# Qwiic-Step.net
KiCad netlist of a schematic drawn in EAGLE
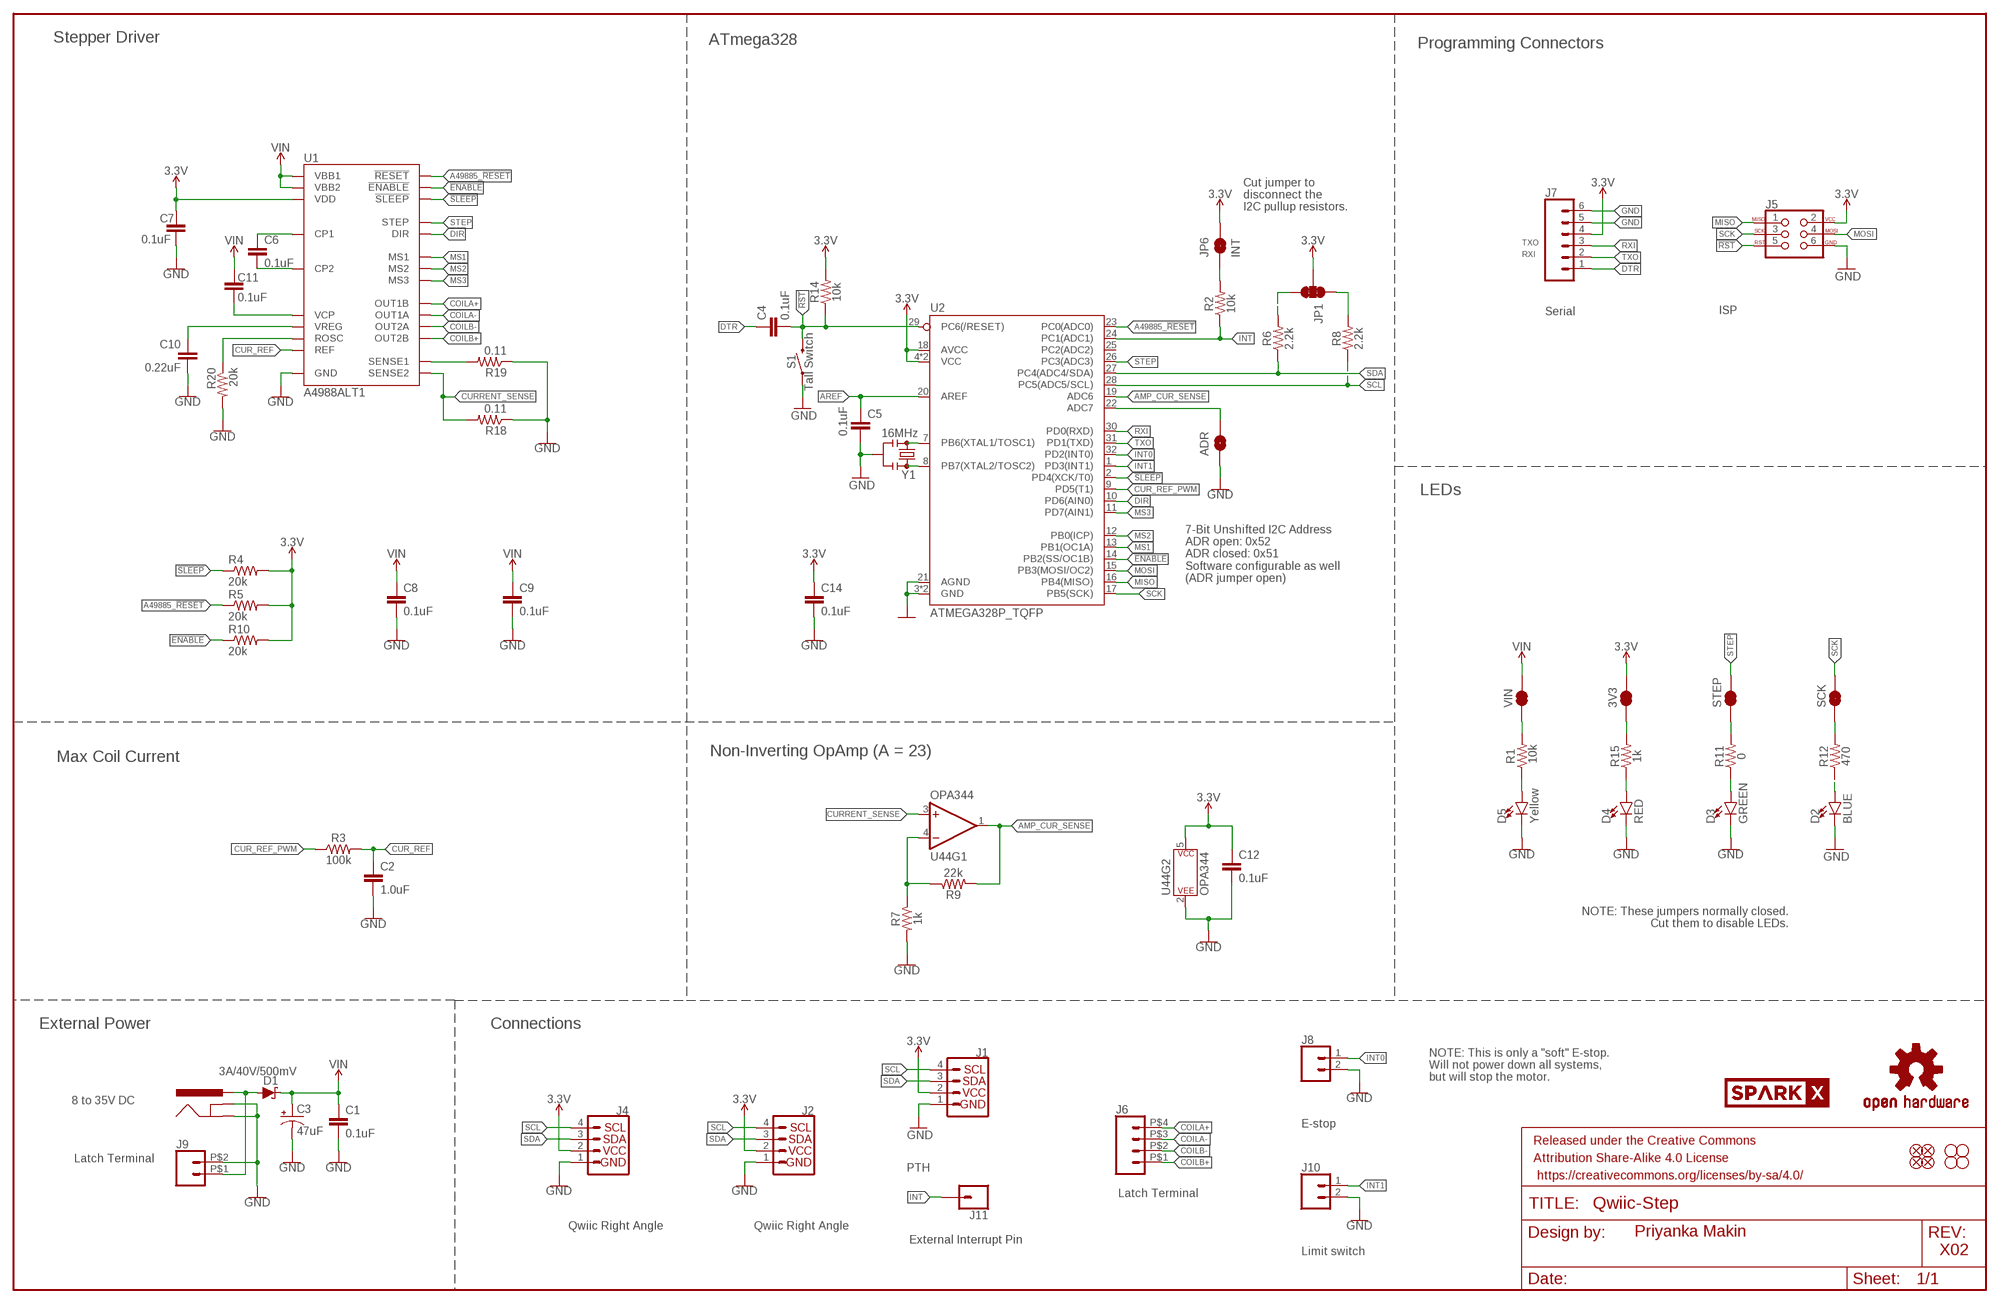
[diagram p0: schematic, sheet 1]

(export (version "E")
  (design (tool "Eeschema 10.0.6"))
  (components
    (comp (ref "3V3")
      (value "JUMPER-SMT_2_NC_TRACE_SILK")
      (footprint "eagle-import:SMT-JUMPER_2_NC_TRACE_SILK")
      (libsource (lib "eagle-import") (part "JUMPER-SMT_2_NC_TRACE_SILK"))
    )
    (comp (ref "ADR")
      (value "ADR")
      (footprint "eagle-import:SMT-JUMPER_2_NO_SILK")
      (libsource (lib "eagle-import") (part "JUMPER-SMT_2_NO_SILK"))
    )
    (comp (ref "C1")
      (value "0.1uF")
      (footprint "eagle-import:0603")
      (libsource (lib "eagle-import") (part "0.1UF-0603-100V-10%"))
    )
    (comp (ref "C2")
      (value "1.0uF")
      (footprint "eagle-import:0603")
      (libsource (lib "eagle-import") (part "1.0UF-0603-16V-10%-X7R"))
    )
    (comp (ref "C3")
      (value "47uF")
      (footprint "eagle-import:PANASONIC_D")
      (libsource (lib "eagle-import") (part "47UF-POLAR-PANASONIC_D-35V-20%"))
    )
    (comp (ref "C4")
      (value "0.1uF")
      (footprint "eagle-import:0603")
      (libsource (lib "eagle-import") (part "0.1UF-0603-100V-10%"))
    )
    (comp (ref "C5")
      (value "0.1uF")
      (footprint "eagle-import:0603")
      (libsource (lib "eagle-import") (part "0.1UF-0603-25V-(+80/-20%)"))
    )
    (comp (ref "C6")
      (value "0.1uF")
      (footprint "eagle-import:0603")
      (libsource (lib "eagle-import") (part "0.1UF-0603-100V-10%"))
    )
    (comp (ref "C7")
      (value "0.1uF")
      (footprint "eagle-import:0603")
      (libsource (lib "eagle-import") (part "0.1UF-0603-25V-(+80/-20%)"))
    )
    (comp (ref "C8")
      (value "0.1uF")
      (footprint "eagle-import:0603")
      (libsource (lib "eagle-import") (part "0.1UF-0603-100V-10%"))
    )
    (comp (ref "C9")
      (value "0.1uF")
      (footprint "eagle-import:0603")
      (libsource (lib "eagle-import") (part "0.1UF-0603-100V-10%"))
    )
    (comp (ref "C10")
      (value "0.22uF")
      (footprint "eagle-import:0603")
      (libsource (lib "eagle-import") (part "0.22UF-0603-50V-(-20/+80%)"))
    )
    (comp (ref "C11")
      (value "0.1uF")
      (footprint "eagle-import:0603")
      (libsource (lib "eagle-import") (part "0.1UF-0603-100V-10%"))
    )
    (comp (ref "C12")
      (value "0.1uF")
      (footprint "eagle-import:0603")
      (libsource (lib "eagle-import") (part "0.1UF-0603-25V-(+80/-20%)"))
    )
    (comp (ref "C14")
      (value "0.1uF")
      (footprint "eagle-import:0603")
      (libsource (lib "eagle-import") (part "0.1UF-0603-25V-(+80/-20%)"))
    )
    (comp (ref "D1")
      (value "3A/40V/500mV")
      (footprint "eagle-import:SMA-DIODE")
      (libsource (lib "eagle-import") (part "DIODE-SCHOTTKY-B340A"))
    )
    (comp (ref "D2")
      (value "BLUE")
      (footprint "eagle-import:LED-0603")
      (libsource (lib "eagle-import") (part "LED-BLUE0603"))
    )
    (comp (ref "D3")
      (value "GREEN")
      (footprint "eagle-import:LED-0603")
      (libsource (lib "eagle-import") (part "LED-GREEN0603"))
    )
    (comp (ref "D4")
      (value "RED")
      (footprint "eagle-import:LED-0603")
      (libsource (lib "eagle-import") (part "LED-RED0603"))
    )
    (comp (ref "D5")
      (value "Yellow")
      (footprint "eagle-import:LED-0603")
      (libsource (lib "eagle-import") (part "LED-YELLOW0603"))
    )
    (comp (ref "FD1")
      (value "FIDUCIAL1X2")
      (footprint "eagle-import:FIDUCIAL-1X2")
      (libsource (lib "eagle-import") (part "FIDUCIAL1X2"))
    )
    (comp (ref "FD2")
      (value "FIDUCIAL1X2")
      (footprint "eagle-import:FIDUCIAL-1X2")
      (libsource (lib "eagle-import") (part "FIDUCIAL1X2"))
    )
    (comp (ref "FD3")
      (value "FIDUCIAL1X2")
      (footprint "eagle-import:FIDUCIAL-1X2")
      (libsource (lib "eagle-import") (part "FIDUCIAL1X2"))
    )
    (comp (ref "FD4")
      (value "FIDUCIAL1X2")
      (footprint "eagle-import:FIDUCIAL-1X2")
      (libsource (lib "eagle-import") (part "FIDUCIAL1X2"))
    )
    (comp (ref "FRAME2")
      (value "FRAME-LEDGER")
      (footprint "eagle-import:CREATIVE_COMMONS")
      (libsource (lib "eagle-import") (part "FRAME-LEDGER"))
    )
    (comp (ref "J1")
      (value "PTH")
      (footprint "eagle-import:1X04_NO_SILK")
      (libsource (lib "eagle-import") (part "SparkX_I2C_STANDARD_NO_SILK"))
    )
    (comp (ref "J2")
      (value "Qwiic Right Angle")
      (footprint "eagle-import:JST04_1MM_RA")
      (libsource (lib "eagle-import") (part "I2C_STANDARDQWIIC"))
    )
    (comp (ref "J3")
      (value "5.5x2.1mm Barrel")
      (footprint "eagle-import:POWER_JACK_SMD")
      (fields (field (name "PROD_ID") "CONN-08106"))
      (libsource (lib "eagle-import") (part "POWER_JACKSMD"))
    )
    (comp (ref "J4")
      (value "Qwiic Right Angle")
      (footprint "eagle-import:JST04_1MM_RA")
      (libsource (lib "eagle-import") (part "I2C_STANDARDQWIIC"))
    )
    (comp (ref "J5")
      (value "ISP")
      (footprint "eagle-import:2X3_TEST_POINTS")
      (libsource (lib "eagle-import") (part "AVR_SPI_PROG_3X2TESTPOINTS"))
    )
    (comp (ref "J6")
      (value "CONN_04LATCH")
      (footprint "eagle-import:LATCHTERMINAL-5MM-4")
      (libsource (lib "eagle-import") (part "CONN_04LATCH"))
    )
    (comp (ref "J7")
      (value "CONN_06NO_SILK_NO_POP")
      (footprint "eagle-import:1X06_NO_SILK")
      (libsource (lib "eagle-import") (part "CONN_06NO_SILK_NO_POP"))
    )
    (comp (ref "J8")
      (value "CONN_02-JST-2MM-SMT")
      (footprint "eagle-import:JST-2-SMD")
      (libsource (lib "eagle-import") (part "CONN_02-JST-2MM-SMT"))
    )
    (comp (ref "J9")
      (value "CONN_02LATCH_2")
      (footprint "eagle-import:LATCHTERMINAL-5MM-2")
      (libsource (lib "eagle-import") (part "CONN_02LATCH_2"))
    )
    (comp (ref "J10")
      (value "CONN_02-JST-2MM-SMT")
      (footprint "eagle-import:JST-2-SMD")
      (libsource (lib "eagle-import") (part "CONN_02-JST-2MM-SMT"))
    )
    (comp (ref "J11")
      (value "CONN_01PTH_NO_SILK_YES_STOP")
      (footprint "eagle-import:1X01_NO_SILK")
      (libsource (lib "eagle-import") (part "CONN_01PTH_NO_SILK_YES_STOP"))
    )
    (comp (ref "JP1")
      (value "JUMPER-SMT_3_2-NC_TRACE_SILK")
      (footprint "eagle-import:SMT-JUMPER_3_2-NC_TRACE_SILK")
      (libsource (lib "eagle-import") (part "JUMPER-SMT_3_2-NC_TRACE_SILK"))
    )
    (comp (ref "JP6")
      (value "INT")
      (footprint "eagle-import:SMT-JUMPER_2_NC_TRACE_SILK")
      (libsource (lib "eagle-import") (part "JUMPER-SMT_2_NC_TRACE_SILK"))
    )
    (comp (ref "JP7")
      (value "STAND-OFF")
      (footprint "eagle-import:STAND-OFF")
      (libsource (lib "eagle-import") (part "STAND-OFF"))
    )
    (comp (ref "JP8")
      (value "STAND-OFF")
      (footprint "eagle-import:STAND-OFF")
      (libsource (lib "eagle-import") (part "STAND-OFF"))
    )
    (comp (ref "JP9")
      (value "STAND-OFF")
      (footprint "eagle-import:STAND-OFF")
      (libsource (lib "eagle-import") (part "STAND-OFF"))
    )
    (comp (ref "JP10")
      (value "STAND-OFF")
      (footprint "eagle-import:STAND-OFF")
      (libsource (lib "eagle-import") (part "STAND-OFF"))
    )
    (comp (ref "LOGO1")
      (value "OSHW-LOGOMINI")
      (footprint "eagle-import:OSHW-LOGO-MINI")
      (libsource (lib "eagle-import") (part "OSHW-LOGOMINI"))
    )
    (comp (ref "R1")
      (value "10k")
      (footprint "eagle-import:0603")
      (libsource (lib "eagle-import") (part "10KOHM-0603-1/10W-1%"))
    )
    (comp (ref "R2")
      (value "10k")
      (footprint "eagle-import:0603")
      (libsource (lib "eagle-import") (part "10KOHM-0603-1/10W-1%"))
    )
    (comp (ref "R3")
      (value "100k")
      (footprint "eagle-import:0603")
      (libsource (lib "eagle-import") (part "100KOHM-0603-1/10W-1%"))
    )
    (comp (ref "R4")
      (value "20k")
      (footprint "eagle-import:0603")
      (libsource (lib "eagle-import") (part "20KOHM-0603-1/10W-1%"))
    )
    (comp (ref "R5")
      (value "20k")
      (footprint "eagle-import:0603")
      (libsource (lib "eagle-import") (part "20KOHM-0603-1/10W-1%"))
    )
    (comp (ref "R6")
      (value "2.2k")
      (footprint "eagle-import:0603")
      (libsource (lib "eagle-import") (part "2.2KOHM-0603-1/10W-1%"))
    )
    (comp (ref "R7")
      (value "1k")
      (footprint "eagle-import:0603")
      (libsource (lib "eagle-import") (part "1KOHM-0603-1/10W-1%"))
    )
    (comp (ref "R8")
      (value "2.2k")
      (footprint "eagle-import:0603")
      (libsource (lib "eagle-import") (part "2.2KOHM-0603-1/10W-1%"))
    )
    (comp (ref "R9")
      (value "22k")
      (footprint "eagle-import:0603")
      (libsource (lib "eagle-import") (part "22KOHM-0603-1/10W-1%"))
    )
    (comp (ref "R10")
      (value "20k")
      (footprint "eagle-import:0603")
      (libsource (lib "eagle-import") (part "20KOHM-0603-1/10W-1%"))
    )
    (comp (ref "R11")
      (value "0")
      (footprint "eagle-import:0603")
      (libsource (lib "eagle-import") (part "0OHM-0603-1/10W"))
    )
    (comp (ref "R12")
      (value "470")
      (footprint "eagle-import:0603")
      (libsource (lib "eagle-import") (part "470OHM-0603-1/10W-1%"))
    )
    (comp (ref "R14")
      (value "10k")
      (footprint "eagle-import:0603")
      (libsource (lib "eagle-import") (part "10KOHM-0603-1/10W-1%"))
    )
    (comp (ref "R15")
      (value "1k")
      (footprint "eagle-import:0603")
      (libsource (lib "eagle-import") (part "1KOHM-0603-1/10W-1%"))
    )
    (comp (ref "R18")
      (value "0.11")
      (footprint "eagle-import:2010")
      (libsource (lib "eagle-import") (part "0.11OHM-2010-1/2W-1%"))
    )
    (comp (ref "R19")
      (value "0.11")
      (footprint "eagle-import:2010")
      (libsource (lib "eagle-import") (part "0.11OHM-2010-1/2W-1%"))
    )
    (comp (ref "R20")
      (value "20k")
      (footprint "eagle-import:0603")
      (libsource (lib "eagle-import") (part "20KOHM-0603-1/10W-1%"))
    )
    (comp (ref "S1")
      (value "Tall Switch")
      (footprint "eagle-import:TACTILE_SWITCH_SMD_5.2MM")
      (libsource (lib "eagle-import") (part "MOMENTARY-SWITCH-SPST-SMD-5.2-TALL-REDUNDANT"))
    )
    (comp (ref "SCK")
      (value "JUMPER-SMT_2_NC_TRACE_SILK")
      (footprint "eagle-import:SMT-JUMPER_2_NC_TRACE_SILK")
      (libsource (lib "eagle-import") (part "JUMPER-SMT_2_NC_TRACE_SILK"))
    )
    (comp (ref "STEP")
      (value "JUMPER-SMT_2_NC_TRACE_SILK")
      (footprint "eagle-import:SMT-JUMPER_2_NC_TRACE_SILK")
      (libsource (lib "eagle-import") (part "JUMPER-SMT_2_NC_TRACE_SILK"))
    )
    (comp (ref "U$49")
      (value "SPARKX-LOGO4")
      (footprint "eagle-import:SPARKX-MEDIUM")
      (libsource (lib "eagle-import") (part "SPARKX-LOGO4"))
    )
    (comp (ref "U1")
      (value "A4988ALT1")
      (footprint "eagle-import:QFN-28-5MM")
      (libsource (lib "eagle-import") (part "A4988ALT1"))
    )
    (comp (ref "U2")
      (value "ATMEGA328P_TQFP")
      (footprint "eagle-import:TQFP32-08")
      (libsource (lib "eagle-import") (part "ATMEGA328P_TQFP"))
    )
    (comp (ref "U44")
      (value "OPA344")
      (footprint "eagle-import:SOT23-5")
      (libsource (lib "eagle-import") (part "OPA344"))
    )
    (comp (ref "VIN")
      (value "JUMPER-SMT_2_NC_TRACE_SILK")
      (footprint "eagle-import:SMT-JUMPER_2_NC_TRACE_SILK")
      (libsource (lib "eagle-import") (part "JUMPER-SMT_2_NC_TRACE_SILK"))
    )
    (comp (ref "Y1")
      (value "16MHz")
      (footprint "eagle-import:RESONATOR-SMD-3.2X1.3")
      (libsource (lib "eagle-import") (part "RESONATOR-16MHZSMD_3.2X1.3"))
    )
  )
  (nets
    (net (code "1") (name "/A49885_~{RESET}") (class "Default")
      (node (ref "R5") (pin "1") (pinfunction "1_1") (pintype "passive"))
      (node (ref "U1") (pin "12") (pinfunction "~{RESET}_12") (pintype "input"))
      (node (ref "U2") (pin "23") (pinfunction "PC0(ADC0)_23") (pintype "bidirectional"))
    )
    (net (code "2") (name "/~{ENABLE}") (class "Default")
      (node (ref "R10") (pin "1") (pinfunction "1_1") (pintype "passive"))
      (node (ref "U1") (pin "2") (pinfunction "~{ENABLE}_2") (pintype "input"))
      (node (ref "U2") (pin "14") (pinfunction "PB2(SS/OC1B)_14") (pintype "bidirectional"))
    )
    (net (code "3") (name "/~{RST}") (class "Default")
      (node (ref "C4") (pin "2") (pinfunction "2_2") (pintype "passive"))
      (node (ref "J5") (pin "5") (pinfunction "5_5") (pintype "passive"))
      (node (ref "R14") (pin "1") (pinfunction "1_1") (pintype "passive"))
      (node (ref "S1") (pin "3") (pinfunction "2_3") (pintype "passive"))
      (node (ref "S1") (pin "4") (pinfunction "2_4") (pintype "passive"))
      (node (ref "U2") (pin "29") (pinfunction "PC6(/RESET)_29") (pintype "bidirectional"))
    )
    (net (code "4") (name "/~{SLEEP}") (class "Default")
      (node (ref "R4") (pin "1") (pinfunction "1_1") (pintype "passive"))
      (node (ref "U1") (pin "14") (pinfunction "~{SLEEP}_14") (pintype "input"))
      (node (ref "U2") (pin "2") (pinfunction "PD4(XCK/T0)_2") (pintype "bidirectional"))
    )
    (net (code "5") (name "3.3V") (class "Default")
      (node (ref "3V3") (pin "2") (pinfunction "2_2") (pintype "passive"))
      (node (ref "C12") (pin "1") (pinfunction "1_1") (pintype "passive"))
      (node (ref "C14") (pin "1") (pinfunction "1_1") (pintype "passive"))
      (node (ref "C7") (pin "1") (pinfunction "1_1") (pintype "passive"))
      (node (ref "J1") (pin "2") (pinfunction "VCC_2") (pintype "power_in"))
      (node (ref "J2") (pin "2") (pinfunction "2_2") (pintype "power_in"))
      (node (ref "J4") (pin "2") (pinfunction "2_2") (pintype "power_in"))
      (node (ref "J5") (pin "2") (pinfunction "2_2") (pintype "passive"))
      (node (ref "J7") (pin "4") (pinfunction "4_4") (pintype "passive"))
      (node (ref "JP1") (pin "2") (pinfunction "2_2") (pintype "passive"))
      (node (ref "JP6") (pin "2") (pinfunction "2_2") (pintype "passive"))
      (node (ref "R10") (pin "2") (pinfunction "2_2") (pintype "passive"))
      (node (ref "R14") (pin "2") (pinfunction "2_2") (pintype "passive"))
      (node (ref "R4") (pin "2") (pinfunction "2_2") (pintype "passive"))
      (node (ref "R5") (pin "2") (pinfunction "2_2") (pintype "passive"))
      (node (ref "U1") (pin "15") (pinfunction "VDD_15") (pintype "power_in"))
      (node (ref "U2") (pin "18") (pinfunction "AVCC_18") (pintype "bidirectional"))
      (node (ref "U2") (pin "4") (pinfunction "VCC_4") (pintype "bidirectional"))
      (node (ref "U2") (pin "6") (pinfunction "VCC_6") (pintype "bidirectional"))
      (node (ref "U44") (pin "5") (pinfunction "P$V+_5") (pintype "bidirectional"))
    )
    (net (code "6") (name "AMP_CUR_SENSE") (class "Default")
      (node (ref "R9") (pin "2") (pinfunction "2_2") (pintype "passive"))
      (node (ref "U2") (pin "19") (pinfunction "ADC6_19") (pintype "bidirectional"))
      (node (ref "U44") (pin "1") (pinfunction "OUT_1") (pintype "output"))
    )
    (net (code "7") (name "AREF") (class "Default")
      (node (ref "C5") (pin "1") (pinfunction "1_1") (pintype "passive"))
      (node (ref "U2") (pin "20") (pinfunction "AREF_20") (pintype "bidirectional"))
    )
    (net (code "8") (name "COILA+") (class "Default")
      (node (ref "J6") (pin "P$4") (pinfunction "4_P$4") (pintype "passive"))
      (node (ref "U1") (pin "21") (pinfunction "OUT1B_21") (pintype "bidirectional"))
    )
    (net (code "9") (name "COILA-") (class "Default")
      (node (ref "J6") (pin "P$3") (pinfunction "3_P$3") (pintype "passive"))
      (node (ref "U1") (pin "24") (pinfunction "OUT1A_24") (pintype "bidirectional"))
    )
    (net (code "10") (name "COILB+") (class "Default")
      (node (ref "J6") (pin "P$1") (pinfunction "1_P$1") (pintype "passive"))
      (node (ref "U1") (pin "1") (pinfunction "OUT2B_1") (pintype "bidirectional"))
    )
    (net (code "11") (name "COILB-") (class "Default")
      (node (ref "J6") (pin "P$2") (pinfunction "2_P$2") (pintype "passive"))
      (node (ref "U1") (pin "26") (pinfunction "OUT2A_26") (pintype "bidirectional"))
    )
    (net (code "12") (name "CURRENT_SENSE") (class "Default")
      (node (ref "R18") (pin "2") (pinfunction "2_2") (pintype "passive"))
      (node (ref "U1") (pin "27") (pinfunction "SENSE2_27") (pintype "bidirectional"))
      (node (ref "U44") (pin "3") (pinfunction "+IN_3") (pintype "input"))
    )
    (net (code "13") (name "CUR_REF") (class "Default")
      (node (ref "C2") (pin "1") (pinfunction "1_1") (pintype "passive"))
      (node (ref "R3") (pin "2") (pinfunction "2_2") (pintype "passive"))
      (node (ref "U1") (pin "17") (pinfunction "REF_17") (pintype "bidirectional"))
    )
    (net (code "14") (name "CUR_REF_PWM") (class "Default")
      (node (ref "R3") (pin "1") (pinfunction "1_1") (pintype "passive"))
      (node (ref "U2") (pin "9") (pinfunction "PD5(T1)_9") (pintype "bidirectional"))
    )
    (net (code "15") (name "DIR") (class "Default")
      (node (ref "U1") (pin "19") (pinfunction "DIR_19") (pintype "input"))
      (node (ref "U2") (pin "10") (pinfunction "PD6(AIN0)_10") (pintype "bidirectional"))
    )
    (net (code "16") (name "DTR") (class "Default")
      (node (ref "C4") (pin "1") (pinfunction "1_1") (pintype "passive"))
      (node (ref "J7") (pin "1") (pinfunction "1_1") (pintype "passive"))
    )
    (net (code "17") (name "GND") (class "Default")
      (node (ref "ADR") (pin "2") (pinfunction "2_2") (pintype "passive"))
      (node (ref "C1") (pin "2") (pinfunction "2_2") (pintype "passive"))
      (node (ref "C10") (pin "2") (pinfunction "2_2") (pintype "passive"))
      (node (ref "C12") (pin "2") (pinfunction "2_2") (pintype "passive"))
      (node (ref "C14") (pin "2") (pinfunction "2_2") (pintype "passive"))
      (node (ref "C2") (pin "2") (pinfunction "2_2") (pintype "passive"))
      (node (ref "C3") (pin "-") (pinfunction "-_-") (pintype "passive"))
      (node (ref "C5") (pin "2") (pinfunction "2_2") (pintype "passive"))
      (node (ref "C7") (pin "2") (pinfunction "2_2") (pintype "passive"))
      (node (ref "C8") (pin "2") (pinfunction "2_2") (pintype "passive"))
      (node (ref "C9") (pin "2") (pinfunction "2_2") (pintype "passive"))
      (node (ref "D2") (pin "C") (pinfunction "C_C") (pintype "passive"))
      (node (ref "D3") (pin "C") (pinfunction "C_C") (pintype "passive"))
      (node (ref "D4") (pin "C") (pinfunction "C_C") (pintype "passive"))
      (node (ref "D5") (pin "C") (pinfunction "C_C") (pintype "passive"))
      (node (ref "J1") (pin "1") (pinfunction "GND_1") (pintype "power_in"))
      (node (ref "J10") (pin "2") (pinfunction "1_2") (pintype "passive"))
      (node (ref "J2") (pin "1") (pinfunction "1_1") (pintype "power_in"))
      (node (ref "J3") (pin "GND") (pinfunction "GNDBREAK_GND") (pintype "bidirectional"))
      (node (ref "J3") (pin "P$4") (pinfunction "GND_P$4") (pintype "bidirectional"))
      (node (ref "J4") (pin "1") (pinfunction "1_1") (pintype "power_in"))
      (node (ref "J5") (pin "6") (pinfunction "6_6") (pintype "passive"))
      (node (ref "J7") (pin "5") (pinfunction "5_5") (pintype "passive"))
      (node (ref "J7") (pin "6") (pinfunction "6_6") (pintype "passive"))
      (node (ref "J8") (pin "2") (pinfunction "1_2") (pintype "passive"))
      (node (ref "J9") (pin "P$2") (pinfunction "2_P$2") (pintype "passive"))
      (node (ref "R18") (pin "1") (pinfunction "1_1") (pintype "passive"))
      (node (ref "R19") (pin "1") (pinfunction "1_1") (pintype "passive"))
      (node (ref "R20") (pin "2") (pinfunction "2_2") (pintype "passive"))
      (node (ref "R7") (pin "2") (pinfunction "2_2") (pintype "passive"))
      (node (ref "S1") (pin "1") (pinfunction "1_1") (pintype "passive"))
      (node (ref "S1") (pin "2") (pinfunction "1_2") (pintype "passive"))
      (node (ref "U1") (pin "18") (pinfunction "GND_18") (pintype "power_in"))
      (node (ref "U1") (pin "29") (pinfunction "GND_29") (pintype "power_in"))
      (node (ref "U1") (pin "3") (pinfunction "GND_3") (pintype "power_in"))
      (node (ref "U2") (pin "21") (pinfunction "AGND_21") (pintype "bidirectional"))
      (node (ref "U2") (pin "3") (pinfunction "GND_3") (pintype "bidirectional"))
      (node (ref "U2") (pin "5") (pinfunction "GND_5") (pintype "bidirectional"))
      (node (ref "U44") (pin "2") (pinfunction "P$V-_2") (pintype "bidirectional"))
      (node (ref "Y1") (pin "2") (pinfunction "2_2") (pintype "passive"))
    )
    (net (code "18") (name "INT") (class "Default")
      (node (ref "J11") (pin "1") (pinfunction "1_1") (pintype "passive"))
      (node (ref "R2") (pin "1") (pinfunction "1_1") (pintype "passive"))
      (node (ref "U2") (pin "24") (pinfunction "PC1(ADC1)_24") (pintype "bidirectional"))
    )
    (net (code "19") (name "INT0") (class "Default")
      (node (ref "J8") (pin "1") (pinfunction "2_1") (pintype "passive"))
      (node (ref "U2") (pin "32") (pinfunction "PD2(INT0)_32") (pintype "bidirectional"))
    )
    (net (code "20") (name "INT1") (class "Default")
      (node (ref "J10") (pin "1") (pinfunction "2_1") (pintype "passive"))
      (node (ref "U2") (pin "1") (pinfunction "PD3(INT1)_1") (pintype "bidirectional"))
    )
    (net (code "21") (name "MISO") (class "Default")
      (node (ref "J5") (pin "1") (pinfunction "1_1") (pintype "passive"))
      (node (ref "U2") (pin "16") (pinfunction "PB4(MISO)_16") (pintype "bidirectional"))
    )
    (net (code "22") (name "MOSI") (class "Default")
      (node (ref "J5") (pin "4") (pinfunction "4_4") (pintype "passive"))
      (node (ref "U2") (pin "15") (pinfunction "PB3(MOSI/OC2)_15") (pintype "bidirectional"))
    )
    (net (code "23") (name "MS1") (class "Default")
      (node (ref "U1") (pin "9") (pinfunction "MS1_9") (pintype "input"))
      (node (ref "U2") (pin "13") (pinfunction "PB1(OC1A)_13") (pintype "bidirectional"))
    )
    (net (code "24") (name "MS2") (class "Default")
      (node (ref "U1") (pin "10") (pinfunction "MS2_10") (pintype "input"))
      (node (ref "U2") (pin "12") (pinfunction "PB0(ICP)_12") (pintype "bidirectional"))
    )
    (net (code "25") (name "MS3") (class "Default")
      (node (ref "U1") (pin "11") (pinfunction "MS3_11") (pintype "input"))
      (node (ref "U2") (pin "11") (pinfunction "PD7(AIN1)_11") (pintype "bidirectional"))
    )
    (net (code "26") (name "Net-(3V3-Pad1)") (class "Default")
      (node (ref "3V3") (pin "1") (pinfunction "1_1") (pintype "passive"))
      (node (ref "R15") (pin "2") (pinfunction "2_2") (pintype "passive"))
    )
    (net (code "27") (name "Net-(D2-PadA)") (class "Default")
      (node (ref "D2") (pin "A") (pinfunction "A_A") (pintype "passive"))
      (node (ref "R12") (pin "1") (pinfunction "1_1") (pintype "passive"))
    )
    (net (code "28") (name "Net-(D3-PadA)") (class "Default")
      (node (ref "D3") (pin "A") (pinfunction "A_A") (pintype "passive"))
      (node (ref "R11") (pin "1") (pinfunction "1_1") (pintype "passive"))
    )
    (net (code "29") (name "Net-(D4-PadA)") (class "Default")
      (node (ref "D4") (pin "A") (pinfunction "A_A") (pintype "passive"))
      (node (ref "R15") (pin "1") (pinfunction "1_1") (pintype "passive"))
    )
    (net (code "30") (name "Net-(D5-PadA)") (class "Default")
      (node (ref "D5") (pin "A") (pinfunction "A_A") (pintype "passive"))
      (node (ref "R1") (pin "1") (pinfunction "1_1") (pintype "passive"))
    )
    (net (code "31") (name "Net-(J3-PWR)") (class "Default")
      (node (ref "D1") (pin "A") (pinfunction "A_A") (pintype "passive"))
      (node (ref "J3") (pin "VIN0") (pinfunction "PWR_VIN0") (pintype "bidirectional"))
      (node (ref "J9") (pin "P$1") (pinfunction "1_P$1") (pintype "passive"))
    )
    (net (code "32") (name "Net-(JP1-Pad1)") (class "Default")
      (node (ref "JP1") (pin "1") (pinfunction "1_1") (pintype "passive"))
      (node (ref "R8") (pin "2") (pinfunction "2_2") (pintype "passive"))
    )
    (net (code "33") (name "Net-(JP1-Pad3)") (class "Default")
      (node (ref "JP1") (pin "3") (pinfunction "3_3") (pintype "passive"))
      (node (ref "R6") (pin "2") (pinfunction "2_2") (pintype "passive"))
    )
    (net (code "34") (name "Net-(JP6-Pad1)") (class "Default")
      (node (ref "JP6") (pin "1") (pinfunction "1_1") (pintype "passive"))
      (node (ref "R2") (pin "2") (pinfunction "2_2") (pintype "passive"))
    )
    (net (code "35") (name "Net-(R1-Pad2)") (class "Default")
      (node (ref "R1") (pin "2") (pinfunction "2_2") (pintype "passive"))
      (node (ref "VIN") (pin "1") (pinfunction "1_1") (pintype "passive"))
    )
    (net (code "36") (name "Net-(R11-Pad2)") (class "Default")
      (node (ref "R11") (pin "2") (pinfunction "2_2") (pintype "passive"))
      (node (ref "STEP") (pin "1") (pinfunction "1_1") (pintype "passive"))
    )
    (net (code "37") (name "Net-(R12-Pad2)") (class "Default")
      (node (ref "R12") (pin "2") (pinfunction "2_2") (pintype "passive"))
      (node (ref "SCK") (pin "1") (pinfunction "1_1") (pintype "passive"))
    )
    (net (code "38") (name "Net-(U1-CP1)") (class "Default")
      (node (ref "C6") (pin "1") (pinfunction "1_1") (pintype "passive"))
      (node (ref "U1") (pin "4") (pinfunction "CP1_4") (pintype "bidirectional"))
    )
    (net (code "39") (name "Net-(U1-CP2)") (class "Default")
      (node (ref "C6") (pin "2") (pinfunction "2_2") (pintype "passive"))
      (node (ref "U1") (pin "5") (pinfunction "CP2_5") (pintype "bidirectional"))
    )
    (net (code "40") (name "Net-(U1-ROSC)") (class "Default")
      (node (ref "R20") (pin "1") (pinfunction "1_1") (pintype "passive"))
      (node (ref "U1") (pin "13") (pinfunction "ROSC_13") (pintype "bidirectional"))
    )
    (net (code "41") (name "Net-(U1-SENSE1)") (class "Default")
      (node (ref "R19") (pin "2") (pinfunction "2_2") (pintype "passive"))
      (node (ref "U1") (pin "23") (pinfunction "SENSE1_23") (pintype "bidirectional"))
    )
    (net (code "42") (name "Net-(U1-VCP)") (class "Default")
      (node (ref "C11") (pin "1") (pinfunction "1_1") (pintype "passive"))
      (node (ref "U1") (pin "6") (pinfunction "VCP_6") (pintype "bidirectional"))
    )
    (net (code "43") (name "Net-(U1-VREG)") (class "Default")
      (node (ref "C10") (pin "1") (pinfunction "1_1") (pintype "passive"))
      (node (ref "U1") (pin "8") (pinfunction "VREG_8") (pintype "bidirectional"))
    )
    (net (code "44") (name "Net-(U2-ADC7)") (class "Default")
      (node (ref "ADR") (pin "1") (pinfunction "1_1") (pintype "passive"))
      (node (ref "U2") (pin "22") (pinfunction "ADC7_22") (pintype "bidirectional"))
    )
    (net (code "45") (name "Net-(U2-PB6(XTAL1{slash}TOSC1))") (class "Default")
      (node (ref "U2") (pin "7") (pinfunction "PB6(XTAL1/TOSC1)_7") (pintype "bidirectional"))
      (node (ref "Y1") (pin "1") (pinfunction "1_1") (pintype "passive"))
    )
    (net (code "46") (name "Net-(U2-PB7(XTAL2{slash}TOSC2))") (class "Default")
      (node (ref "U2") (pin "8") (pinfunction "PB7(XTAL2/TOSC2)_8") (pintype "bidirectional"))
      (node (ref "Y1") (pin "3") (pinfunction "3_3") (pintype "passive"))
    )
    (net (code "47") (name "Net-(U44A--IN)") (class "Default")
      (node (ref "R7") (pin "1") (pinfunction "1_1") (pintype "passive"))
      (node (ref "R9") (pin "1") (pinfunction "1_1") (pintype "passive"))
      (node (ref "U44") (pin "4") (pinfunction "-IN_4") (pintype "input"))
    )
    (net (code "48") (name "RXI") (class "Default")
      (node (ref "J7") (pin "3") (pinfunction "3_3") (pintype "passive"))
      (node (ref "U2") (pin "30") (pinfunction "PD0(RXD)_30") (pintype "bidirectional"))
    )
    (net (code "49") (name "SCK") (class "Default")
      (node (ref "J5") (pin "3") (pinfunction "3_3") (pintype "passive"))
      (node (ref "SCK") (pin "2") (pinfunction "2_2") (pintype "passive"))
      (node (ref "U2") (pin "17") (pinfunction "PB5(SCK)_17") (pintype "bidirectional"))
    )
    (net (code "50") (name "SCL") (class "Default")
      (node (ref "J1") (pin "4") (pinfunction "SCL_4") (pintype "passive"))
      (node (ref "J2") (pin "4") (pinfunction "4_4") (pintype "passive"))
      (node (ref "J4") (pin "4") (pinfunction "4_4") (pintype "passive"))
      (node (ref "R8") (pin "1") (pinfunction "1_1") (pintype "passive"))
      (node (ref "U2") (pin "28") (pinfunction "PC5(ADC5/SCL)_28") (pintype "bidirectional"))
    )
    (net (code "51") (name "SDA") (class "Default")
      (node (ref "J1") (pin "3") (pinfunction "SDA_3") (pintype "passive"))
      (node (ref "J2") (pin "3") (pinfunction "3_3") (pintype "passive"))
      (node (ref "J4") (pin "3") (pinfunction "3_3") (pintype "passive"))
      (node (ref "R6") (pin "1") (pinfunction "1_1") (pintype "passive"))
      (node (ref "U2") (pin "27") (pinfunction "PC4(ADC4/SDA)_27") (pintype "bidirectional"))
    )
    (net (code "52") (name "STEP") (class "Default")
      (node (ref "STEP") (pin "2") (pinfunction "2_2") (pintype "passive"))
      (node (ref "U1") (pin "16") (pinfunction "STEP_16") (pintype "input"))
      (node (ref "U2") (pin "26") (pinfunction "PC3(ADC3)_26") (pintype "bidirectional"))
    )
    (net (code "53") (name "TXO") (class "Default")
      (node (ref "J7") (pin "2") (pinfunction "2_2") (pintype "passive"))
      (node (ref "U2") (pin "31") (pinfunction "PD1(TXD)_31") (pintype "bidirectional"))
    )
    (net (code "54") (name "VIN") (class "Default")
      (node (ref "C1") (pin "1") (pinfunction "1_1") (pintype "passive"))
      (node (ref "C11") (pin "2") (pinfunction "2_2") (pintype "passive"))
      (node (ref "C3") (pin "+") (pinfunction "+_+") (pintype "passive"))
      (node (ref "C8") (pin "1") (pinfunction "1_1") (pintype "passive"))
      (node (ref "C9") (pin "1") (pinfunction "1_1") (pintype "passive"))
      (node (ref "D1") (pin "C") (pinfunction "C_C") (pintype "passive"))
      (node (ref "U1") (pin "22") (pinfunction "VBB1_22") (pintype "bidirectional"))
      (node (ref "U1") (pin "28") (pinfunction "VBB2_28") (pintype "bidirectional"))
      (node (ref "VIN") (pin "2") (pinfunction "2_2") (pintype "passive"))
    )
    (net (code "55") (name "unconnected-(U2-PC2(ADC2)-Pad25)") (class "Default")
      (node (ref "U2") (pin "25") (pinfunction "PC2(ADC2)_25") (pintype "bidirectional"))
    )
  )
)
